# driver.net
KiCad netlist of a schematic drawn in EAGLE
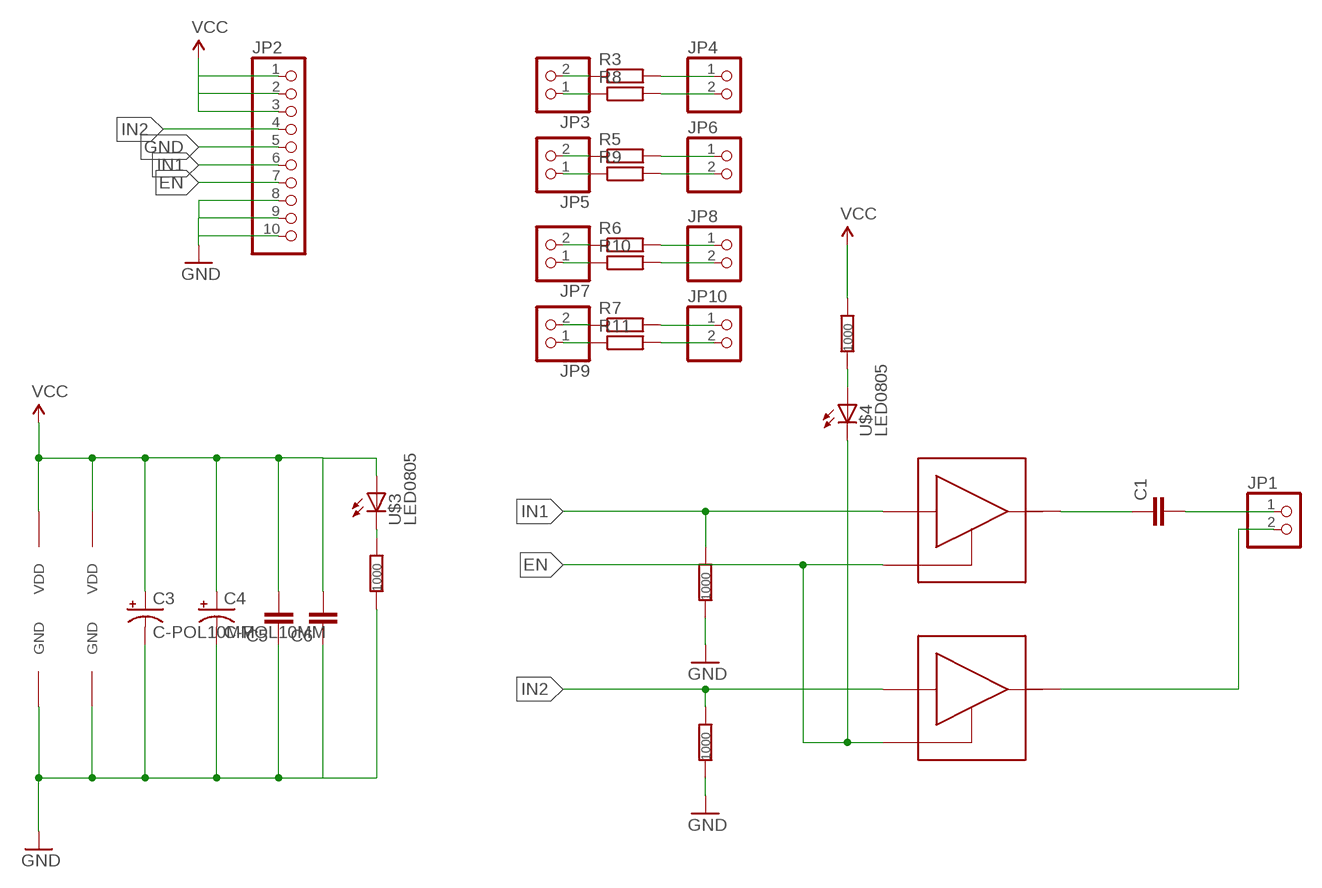
[diagram p0: schematic, sheet 1]

(export (version "E")
  (design (tool "Eeschema 10.0.6"))
  (components
    (comp (ref "C1")
      (value "CC2220K")
      (footprint "eagle-import:C2220K")
      (libsource (lib "eagle-import") (part "CC2220K"))
    )
    (comp (ref "C3")
      (value "C-POL10MM")
      (footprint "eagle-import:PCAP10")
      (libsource (lib "eagle-import") (part "C-POL10MM"))
    )
    (comp (ref "C4")
      (value "C-POL10MM")
      (footprint "eagle-import:PCAP10")
      (libsource (lib "eagle-import") (part "C-POL10MM"))
    )
    (comp (ref "C5")
      (value "CC2220K")
      (footprint "eagle-import:C2220K")
      (libsource (lib "eagle-import") (part "CC2220K"))
    )
    (comp (ref "C6")
      (value "CC2220K")
      (footprint "eagle-import:C2220K")
      (libsource (lib "eagle-import") (part "CC2220K"))
    )
    (comp (ref "JP1")
      (value "PINHD-1X2")
      (footprint "eagle-import:1X02")
      (libsource (lib "eagle-import") (part "PINHD-1X2"))
    )
    (comp (ref "JP2")
      (value "PINHD-1X10")
      (footprint "eagle-import:1X10")
      (libsource (lib "eagle-import") (part "PINHD-1X10"))
    )
    (comp (ref "JP3")
      (value "PINHD-1X2")
      (footprint "eagle-import:1X02")
      (libsource (lib "eagle-import") (part "PINHD-1X2"))
    )
    (comp (ref "JP4")
      (value "PINHD-1X2")
      (footprint "eagle-import:1X02")
      (libsource (lib "eagle-import") (part "PINHD-1X2"))
    )
    (comp (ref "JP5")
      (value "PINHD-1X2")
      (footprint "eagle-import:1X02")
      (libsource (lib "eagle-import") (part "PINHD-1X2"))
    )
    (comp (ref "JP6")
      (value "PINHD-1X2")
      (footprint "eagle-import:1X02")
      (libsource (lib "eagle-import") (part "PINHD-1X2"))
    )
    (comp (ref "JP7")
      (value "PINHD-1X2")
      (footprint "eagle-import:1X02")
      (libsource (lib "eagle-import") (part "PINHD-1X2"))
    )
    (comp (ref "JP8")
      (value "PINHD-1X2")
      (footprint "eagle-import:1X02")
      (libsource (lib "eagle-import") (part "PINHD-1X2"))
    )
    (comp (ref "JP9")
      (value "PINHD-1X2")
      (footprint "eagle-import:1X02")
      (libsource (lib "eagle-import") (part "PINHD-1X2"))
    )
    (comp (ref "JP10")
      (value "PINHD-1X2")
      (footprint "eagle-import:1X02")
      (libsource (lib "eagle-import") (part "PINHD-1X2"))
    )
    (comp (ref "R1")
      (value "1000")
      (footprint "eagle-import:R0805")
      (libsource (lib "eagle-import") (part "R0805"))
    )
    (comp (ref "R2")
      (value "1000")
      (footprint "eagle-import:R0805")
      (libsource (lib "eagle-import") (part "R0805"))
    )
    (comp (ref "R3")
      (value "R-EU_0204/7")
      (footprint "eagle-import:0204_7")
      (libsource (lib "eagle-import") (part "R-EU_0204/7"))
    )
    (comp (ref "R4")
      (value "1000")
      (footprint "eagle-import:R0805")
      (libsource (lib "eagle-import") (part "R0805"))
    )
    (comp (ref "R5")
      (value "R-EU_0204/7")
      (footprint "eagle-import:0204_7")
      (libsource (lib "eagle-import") (part "R-EU_0204/7"))
    )
    (comp (ref "R6")
      (value "R-EU_0204/7")
      (footprint "eagle-import:0204_7")
      (libsource (lib "eagle-import") (part "R-EU_0204/7"))
    )
    (comp (ref "R7")
      (value "R-EU_0204/7")
      (footprint "eagle-import:0204_7")
      (libsource (lib "eagle-import") (part "R-EU_0204/7"))
    )
    (comp (ref "R8")
      (value "R-EU_0204/7")
      (footprint "eagle-import:0204_7")
      (libsource (lib "eagle-import") (part "R-EU_0204/7"))
    )
    (comp (ref "R9")
      (value "R-EU_0204/7")
      (footprint "eagle-import:0204_7")
      (libsource (lib "eagle-import") (part "R-EU_0204/7"))
    )
    (comp (ref "R10")
      (value "R-EU_0204/7")
      (footprint "eagle-import:0204_7")
      (libsource (lib "eagle-import") (part "R-EU_0204/7"))
    )
    (comp (ref "R11")
      (value "R-EU_0204/7")
      (footprint "eagle-import:0204_7")
      (libsource (lib "eagle-import") (part "R-EU_0204/7"))
    )
    (comp (ref "R12")
      (value "1000")
      (footprint "eagle-import:R0805")
      (libsource (lib "eagle-import") (part "R0805"))
    )
    (comp (ref "U$1")
      (value "IXDD614")
      (footprint "eagle-import:DPACK-5")
      (libsource (lib "eagle-import") (part "IXDD614"))
    )
    (comp (ref "U$2")
      (value "IXDD614")
      (footprint "eagle-import:DPACK-5")
      (libsource (lib "eagle-import") (part "IXDD614"))
    )
    (comp (ref "U$3")
      (value "LED0805")
      (footprint "eagle-import:0805-LED")
      (libsource (lib "eagle-import") (part "LED0805"))
    )
    (comp (ref "U$4")
      (value "LED0805")
      (footprint "eagle-import:0805-LED")
      (libsource (lib "eagle-import") (part "LED0805"))
    )
  )
  (nets
    (net (code "1") (name "EN") (class "Default")
      (node (ref "JP2") (pin "7") (pinfunction "7_7") (pintype "passive"))
      (node (ref "U$1") (pin "5") (pinfunction "EN_5") (pintype "bidirectional"))
      (node (ref "U$2") (pin "5") (pinfunction "EN_5") (pintype "bidirectional"))
      (node (ref "U$4") (pin "C") (pinfunction "C_C") (pintype "passive"))
    )
    (net (code "2") (name "GND") (class "Default")
      (node (ref "C3") (pin "P$2") (pinfunction "-_P$2") (pintype "passive"))
      (node (ref "C4") (pin "P$2") (pinfunction "-_P$2") (pintype "passive"))
      (node (ref "C5") (pin "1") (pinfunction "1_1") (pintype "passive"))
      (node (ref "C6") (pin "1") (pinfunction "1_1") (pintype "passive"))
      (node (ref "JP2") (pin "10") (pinfunction "10_10") (pintype "passive"))
      (node (ref "JP2") (pin "5") (pinfunction "5_5") (pintype "passive"))
      (node (ref "JP2") (pin "8") (pinfunction "8_8") (pintype "passive"))
      (node (ref "JP2") (pin "9") (pinfunction "9_9") (pintype "passive"))
      (node (ref "R1") (pin "1") (pinfunction "1_1") (pintype "passive"))
      (node (ref "R12") (pin "1") (pinfunction "1_1") (pintype "passive"))
      (node (ref "R2") (pin "1") (pinfunction "1_1") (pintype "passive"))
      (node (ref "U$1") (pin "3") (pinfunction "GND_3") (pintype "power_in"))
      (node (ref "U$1") (pin "6") (pinfunction "GND_6") (pintype "power_in"))
      (node (ref "U$2") (pin "3") (pinfunction "GND_3") (pintype "power_in"))
      (node (ref "U$2") (pin "6") (pinfunction "GND_6") (pintype "power_in"))
    )
    (net (code "3") (name "IN1") (class "Default")
      (node (ref "JP2") (pin "6") (pinfunction "6_6") (pintype "passive"))
      (node (ref "R1") (pin "2") (pinfunction "2_2") (pintype "passive"))
      (node (ref "U$1") (pin "4") (pinfunction "IN_4") (pintype "bidirectional"))
    )
    (net (code "4") (name "IN2") (class "Default")
      (node (ref "JP2") (pin "4") (pinfunction "4_4") (pintype "passive"))
      (node (ref "R2") (pin "2") (pinfunction "2_2") (pintype "passive"))
      (node (ref "U$2") (pin "4") (pinfunction "IN_4") (pintype "bidirectional"))
    )
    (net (code "5") (name "Net-(C1-Pad2)") (class "Default")
      (node (ref "C1") (pin "2") (pinfunction "2_2") (pintype "passive"))
      (node (ref "JP1") (pin "1") (pinfunction "1_1") (pintype "passive"))
    )
    (net (code "6") (name "Net-(JP3-Pad1)") (class "Default")
      (node (ref "JP3") (pin "1") (pinfunction "1_1") (pintype "passive"))
      (node (ref "R8") (pin "1") (pinfunction "1_1") (pintype "passive"))
    )
    (net (code "7") (name "Net-(JP3-Pad2)") (class "Default")
      (node (ref "JP3") (pin "2") (pinfunction "2_2") (pintype "passive"))
      (node (ref "R3") (pin "1") (pinfunction "1_1") (pintype "passive"))
    )
    (net (code "8") (name "Net-(JP4-Pad1)") (class "Default")
      (node (ref "JP4") (pin "1") (pinfunction "1_1") (pintype "passive"))
      (node (ref "R3") (pin "2") (pinfunction "2_2") (pintype "passive"))
    )
    (net (code "9") (name "Net-(JP4-Pad2)") (class "Default")
      (node (ref "JP4") (pin "2") (pinfunction "2_2") (pintype "passive"))
      (node (ref "R8") (pin "2") (pinfunction "2_2") (pintype "passive"))
    )
    (net (code "10") (name "Net-(JP5-Pad1)") (class "Default")
      (node (ref "JP5") (pin "1") (pinfunction "1_1") (pintype "passive"))
      (node (ref "R9") (pin "1") (pinfunction "1_1") (pintype "passive"))
    )
    (net (code "11") (name "Net-(JP5-Pad2)") (class "Default")
      (node (ref "JP5") (pin "2") (pinfunction "2_2") (pintype "passive"))
      (node (ref "R5") (pin "1") (pinfunction "1_1") (pintype "passive"))
    )
    (net (code "12") (name "Net-(JP6-Pad1)") (class "Default")
      (node (ref "JP6") (pin "1") (pinfunction "1_1") (pintype "passive"))
      (node (ref "R5") (pin "2") (pinfunction "2_2") (pintype "passive"))
    )
    (net (code "13") (name "Net-(JP6-Pad2)") (class "Default")
      (node (ref "JP6") (pin "2") (pinfunction "2_2") (pintype "passive"))
      (node (ref "R9") (pin "2") (pinfunction "2_2") (pintype "passive"))
    )
    (net (code "14") (name "Net-(JP7-Pad1)") (class "Default")
      (node (ref "JP7") (pin "1") (pinfunction "1_1") (pintype "passive"))
      (node (ref "R10") (pin "1") (pinfunction "1_1") (pintype "passive"))
    )
    (net (code "15") (name "Net-(JP7-Pad2)") (class "Default")
      (node (ref "JP7") (pin "2") (pinfunction "2_2") (pintype "passive"))
      (node (ref "R6") (pin "1") (pinfunction "1_1") (pintype "passive"))
    )
    (net (code "16") (name "Net-(JP8-Pad1)") (class "Default")
      (node (ref "JP8") (pin "1") (pinfunction "1_1") (pintype "passive"))
      (node (ref "R6") (pin "2") (pinfunction "2_2") (pintype "passive"))
    )
    (net (code "17") (name "Net-(JP8-Pad2)") (class "Default")
      (node (ref "JP8") (pin "2") (pinfunction "2_2") (pintype "passive"))
      (node (ref "R10") (pin "2") (pinfunction "2_2") (pintype "passive"))
    )
    (net (code "18") (name "Net-(JP9-Pad1)") (class "Default")
      (node (ref "JP9") (pin "1") (pinfunction "1_1") (pintype "passive"))
      (node (ref "R11") (pin "1") (pinfunction "1_1") (pintype "passive"))
    )
    (net (code "19") (name "Net-(JP9-Pad2)") (class "Default")
      (node (ref "JP9") (pin "2") (pinfunction "2_2") (pintype "passive"))
      (node (ref "R7") (pin "1") (pinfunction "1_1") (pintype "passive"))
    )
    (net (code "20") (name "Net-(JP10-Pad1)") (class "Default")
      (node (ref "JP10") (pin "1") (pinfunction "1_1") (pintype "passive"))
      (node (ref "R7") (pin "2") (pinfunction "2_2") (pintype "passive"))
    )
    (net (code "21") (name "Net-(JP10-Pad2)") (class "Default")
      (node (ref "JP10") (pin "2") (pinfunction "2_2") (pintype "passive"))
      (node (ref "R11") (pin "2") (pinfunction "2_2") (pintype "passive"))
    )
    (net (code "22") (name "Net-(R4-Pad1)") (class "Default")
      (node (ref "R4") (pin "1") (pinfunction "1_1") (pintype "passive"))
      (node (ref "U$4") (pin "A") (pinfunction "A_A") (pintype "passive"))
    )
    (net (code "23") (name "Net-(R12-Pad2)") (class "Default")
      (node (ref "R12") (pin "2") (pinfunction "2_2") (pintype "passive"))
      (node (ref "U$3") (pin "C") (pinfunction "C_C") (pintype "passive"))
    )
    (net (code "24") (name "Net-(U$1A-OUT)") (class "Default")
      (node (ref "C1") (pin "1") (pinfunction "1_1") (pintype "passive"))
      (node (ref "U$1") (pin "2") (pinfunction "OUT_2") (pintype "bidirectional"))
    )
    (net (code "25") (name "Net-(U$2A-OUT)") (class "Default")
      (node (ref "JP1") (pin "2") (pinfunction "2_2") (pintype "passive"))
      (node (ref "U$2") (pin "2") (pinfunction "OUT_2") (pintype "bidirectional"))
    )
    (net (code "26") (name "VCC") (class "Default")
      (node (ref "C3") (pin "P$1") (pinfunction "+_P$1") (pintype "passive"))
      (node (ref "C4") (pin "P$1") (pinfunction "+_P$1") (pintype "passive"))
      (node (ref "C5") (pin "2") (pinfunction "2_2") (pintype "passive"))
      (node (ref "C6") (pin "2") (pinfunction "2_2") (pintype "passive"))
      (node (ref "JP2") (pin "1") (pinfunction "1_1") (pintype "passive"))
      (node (ref "JP2") (pin "2") (pinfunction "2_2") (pintype "passive"))
      (node (ref "JP2") (pin "3") (pinfunction "3_3") (pintype "passive"))
      (node (ref "R4") (pin "2") (pinfunction "2_2") (pintype "passive"))
      (node (ref "U$1") (pin "1") (pinfunction "VDD_1") (pintype "power_in"))
      (node (ref "U$2") (pin "1") (pinfunction "VDD_1") (pintype "power_in"))
      (node (ref "U$3") (pin "A") (pinfunction "A_A") (pintype "passive"))
    )
  )
)
